# AA_Tone_Control.net
KiCad netlist of a schematic drawn in Altium Designer
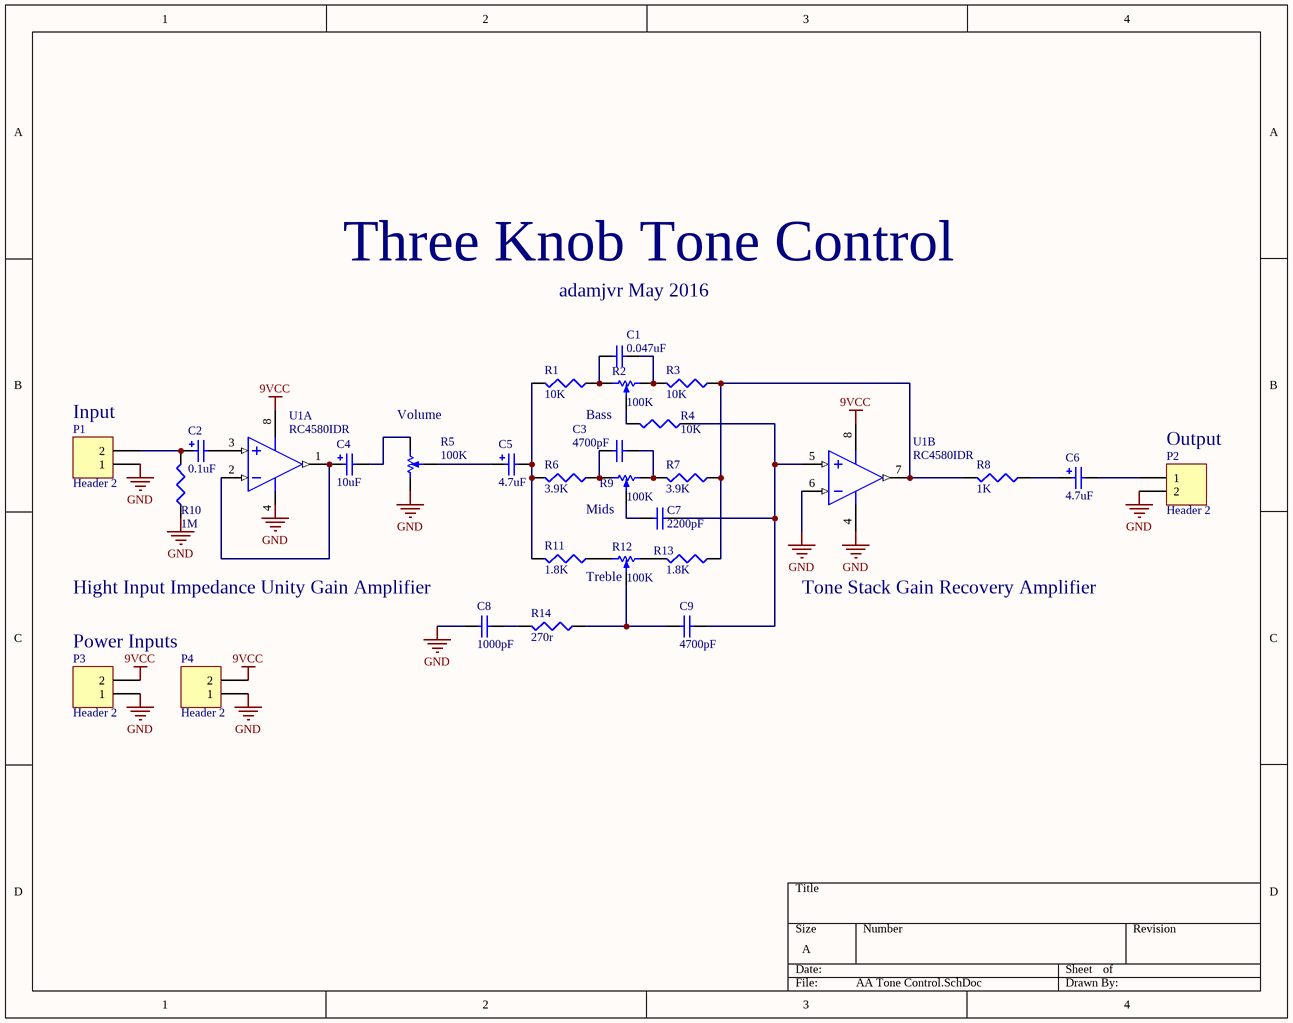
[diagram p0: AA Tone Control.SchDoc]

(export (version "E")
  (design (tool "Eeschema 10.0.6"))
  (components
    (comp (ref "C1")
      (value "0.047uF")
      (footprint "K473K15X7RF5TH5")
      (fields
        (field (name "MFR") "Vishay BC Components")
        (field (name "TOLERANCE") "10%")
        (field (name "VOLTAGE") "50V")
        (field (name "DESIGNER") "Adam Vadala-Roth")
      )
      (libsource (lib "AudioPartLib") (part "K473K15X7RF5TH5"))
    )
    (comp (ref "C2")
      (value "0.1uF")
      (footprint "4X6mmCAP")
      (description "CAP ALUM 0.1UF 20% 50V RADIAL")
      (fields
        (field (name "MFR") "Nichion")
        (field (name "TOLERANCE") "20%")
        (field (name "DESIGNER") "Adam Vadala-Roth")
      )
      (libsource (lib "AudioPartLib") (part "UMW1H0R1MDD1TP"))
    )
    (comp (ref "C3")
      (value "4700pF")
      (footprint "VY2472M49Y5US63V7")
      (fields
        (field (name "MFR") "Vishay-BC-Components")
        (field (name "TOLERANCE") "20%")
        (field (name "VOLTAGE") "440VAC")
        (field (name "DESIGNER") "Adam Vadala-Roth")
      )
      (libsource (lib "AudioPartLib") (part "VY2472M49Y5US63V7"))
    )
    (comp (ref "C4")
      (value "10uF")
      (footprint "5X12.5mmCAP - GREEN")
      (description "CAP ALUM 10UF 20% 25V RADIAL")
      (fields
        (field (name "MFR") "Nichicon")
        (field (name "TOLERANCE") "20%")
        (field (name "DESIGNER") "Adam Vadala-Roth")
      )
      (libsource (lib "AudioPartLib") (part "UES1E100MDM1TD"))
    )
    (comp (ref "C5")
      (value "4.7uF")
      (footprint "4X6mmCAP")
      (description "CAP ALUM 4.7UF 20% 35V RADIAL")
      (fields
        (field (name "MFR") "Nichicon")
        (field (name "TOLERANCE") "20%")
        (field (name "DESIGNER") "Adam Vadala-Roth")
      )
      (libsource (lib "AudioPartLib") (part "UMW1V4R7MDD1TP"))
    )
    (comp (ref "C6")
      (value "4.7uF")
      (footprint "4X6mmCAP")
      (description "CAP ALUM 4.7UF 20% 35V RADIAL")
      (fields
        (field (name "MFR") "Nichicon")
        (field (name "TOLERANCE") "20%")
        (field (name "DESIGNER") "Adam Vadala-Roth")
      )
      (libsource (lib "AudioPartLib") (part "UMW1V4R7MDD1TP"))
    )
    (comp (ref "C7")
      (value "2200pF")
      (footprint "VY1222M47Y5UQ63V0")
      (fields
        (field (name "MFR") "Vishay-BC-Components")
        (field (name "TOLERANCE") "20%")
        (field (name "VOLTAGE") "760VAC")
        (field (name "DESIGNER") "Adam Vadala-Roth")
      )
      (libsource (lib "AudioPartLib") (part "VY1222M47Y5UQ63V0"))
    )
    (comp (ref "C8")
      (value "1000pF")
      (footprint "VY2102M29Y5US63V7")
      (fields
        (field (name "MFR") "Vishay-BC-Components")
        (field (name "TOLERANCE") "20%")
        (field (name "VOLTAGE") "440VAC")
        (field (name "DESIGNER") "Adam Vadala-Roth")
      )
      (libsource (lib "AudioPartLib") (part "VY2102M29Y5US63V7"))
    )
    (comp (ref "C9")
      (value "4700pF")
      (footprint "VY2472M49Y5US63V7")
      (fields
        (field (name "MFR") "Vishay-BC-Components")
        (field (name "TOLERANCE") "20%")
        (field (name "VOLTAGE") "440VAC")
        (field (name "DESIGNER") "Adam Vadala-Roth")
      )
      (libsource (lib "AudioPartLib") (part "VY2472M49Y5US63V7"))
    )
    (comp (ref "P1")
      (value "Header 2")
      (footprint "HDR1X2")
      (description "Header, 2-Pin")
      (fields (field (name "PUBLISHER") "Altium Limited"))
      (libsource (lib "") (part "Header 2_1"))
    )
    (comp (ref "P2")
      (value "Header 2")
      (footprint "HDR1X2")
      (description "Header, 2-Pin")
      (fields (field (name "PUBLISHER") "Altium Limited"))
      (libsource (lib "Miscellaneous Connectors") (part "Header 2"))
    )
    (comp (ref "P3")
      (value "Header 2")
      (footprint "HDR1X2")
      (description "Header, 2-Pin")
      (fields (field (name "PUBLISHER") "Altium Limited"))
      (libsource (lib "") (part "Header 2_1"))
    )
    (comp (ref "P4")
      (value "Header 2")
      (footprint "HDR1X2")
      (description "Header, 2-Pin")
      (fields (field (name "PUBLISHER") "Altium Limited"))
      (libsource (lib "") (part "Header 2_1"))
    )
    (comp (ref "R1")
      (value "10K")
      (footprint "R0805")
      (description "RES SMD 10K OHM 1% 1/8W 0805")
      (fields
        (field (name "MFR") "Panasonic-Electronic-Components")
        (field (name "TOLERANCE") "1%")
        (field (name "DESIGNER") "Adam Vadala-Roth")
      )
      (libsource (lib "AudioPartLib") (part "ERJ-6ENF1002V"))
    )
    (comp (ref "R2")
      (value "100K")
      (footprint "BOURNS_PTD90SERIES_POT")
      (description "POT 100K OHM 1/20W CARBON LINEAR")
      (fields
        (field (name "MFR") "Bourns Inc.")
        (field (name "TOLERANCE") "20%")
        (field (name "DESIGNER") "Adam Vadala-Roth")
      )
      (libsource (lib "AudioPartLib") (part "PTD901-2015K-B104"))
    )
    (comp (ref "R3")
      (value "10K")
      (footprint "R0805")
      (description "RES SMD 10K OHM 1% 1/8W 0805")
      (fields
        (field (name "MFR") "Panasonic-Electronic-Components")
        (field (name "TOLERANCE") "1%")
        (field (name "DESIGNER") "Adam Vadala-Roth")
      )
      (libsource (lib "AudioPartLib") (part "ERJ-6ENF1002V"))
    )
    (comp (ref "R4")
      (value "10K")
      (footprint "R0805")
      (description "RES SMD 10K OHM 1% 1/8W 0805")
      (fields
        (field (name "MFR") "Panasonic-Electronic-Components")
        (field (name "TOLERANCE") "1%")
        (field (name "DESIGNER") "Adam Vadala-Roth")
      )
      (libsource (lib "AudioPartLib") (part "ERJ-6ENF1002V"))
    )
    (comp (ref "R5")
      (value "100K")
      (footprint "BOURNS_PTD90SERIES_POT")
      (description "POT 100K OHM 1/20W CARBON LINEAR")
      (fields
        (field (name "MFR") "Bourns Inc.")
        (field (name "TOLERANCE") "20%")
        (field (name "DESIGNER") "Adam Vadala-Roth")
      )
      (libsource (lib "AudioPartLib") (part "PTD901-2015K-B104"))
    )
    (comp (ref "R6")
      (value "3.9K")
      (footprint "R0805")
      (description "RES SMD 3.9K OHM 1% 1/8W 0805")
      (fields
        (field (name "MFR") "Samsung-Electro-Mechanics-America,-Inc.")
        (field (name "TOLERANCE") "1%")
        (field (name "DESIGNER") "Adam Vadala-Roth")
      )
      (libsource (lib "AudioPartLib") (part "RC2012F392CS"))
    )
    (comp (ref "R7")
      (value "3.9K")
      (footprint "R0805")
      (description "RES SMD 3.9K OHM 1% 1/8W 0805")
      (fields
        (field (name "MFR") "Samsung-Electro-Mechanics-America,-Inc.")
        (field (name "TOLERANCE") "1%")
        (field (name "DESIGNER") "Adam Vadala-Roth")
      )
      (libsource (lib "AudioPartLib") (part "RC2012F392CS"))
    )
    (comp (ref "R8")
      (value "1K")
      (footprint "R0805")
      (description "RES SMD 1K OHM 1% 1/8W 0805")
      (fields
        (field (name "MFR") "Samsung-Electro-Mechanics-America,-Inc.")
        (field (name "TOLERANCE") "1%")
        (field (name "DESIGNER") "Adam Vadala-Roth")
      )
      (libsource (lib "AudioPartLib") (part "RC2012F102CS"))
    )
    (comp (ref "R9")
      (value "100K")
      (footprint "BOURNS_PTD90SERIES_POT")
      (description "POT 100K OHM 1/20W CARBON LINEAR")
      (fields
        (field (name "MFR") "Bourns Inc.")
        (field (name "TOLERANCE") "20%")
        (field (name "DESIGNER") "Adam Vadala-Roth")
      )
      (libsource (lib "AudioPartLib") (part "PTD901-2015K-B104"))
    )
    (comp (ref "R10")
      (value "1M")
      (footprint "R0805")
      (description "RES SMD 1M OHM 5% 1/8W 0805")
      (fields
        (field (name "MFR") "Samsung-Electro-Mechanics-America,-Inc.")
        (field (name "TOLERANCE") "5%")
        (field (name "DESIGNER") "Adam Vadala-Roth")
      )
      (libsource (lib "AudioPartLib") (part "RC2012J105CS"))
    )
    (comp (ref "R11")
      (value "1.8K")
      (footprint "R0805")
      (description "RES SMD 1.8K OHM 1% 1/8W 0805")
      (fields
        (field (name "MFR") "Samsung-Electro-Mechanics-America,-Inc.")
        (field (name "TOLERANCE") "1%")
        (field (name "DESIGNER") "Adam Vadala-Roth")
      )
      (libsource (lib "AudioPartLib") (part "RC2012F182CS"))
    )
    (comp (ref "R12")
      (value "100K")
      (footprint "BOURNS_PTD90SERIES_POT")
      (description "POT 100K OHM 1/20W CARBON LINEAR")
      (fields
        (field (name "MFR") "Bourns Inc.")
        (field (name "TOLERANCE") "20%")
        (field (name "DESIGNER") "Adam Vadala-Roth")
      )
      (libsource (lib "AudioPartLib") (part "PTD901-2015K-B104"))
    )
    (comp (ref "R13")
      (value "1.8K")
      (footprint "R0805")
      (description "RES SMD 1.8K OHM 1% 1/8W 0805")
      (fields
        (field (name "MFR") "Samsung-Electro-Mechanics-America,-Inc.")
        (field (name "TOLERANCE") "1%")
        (field (name "DESIGNER") "Adam Vadala-Roth")
      )
      (libsource (lib "AudioPartLib") (part "RC2012F182CS"))
    )
    (comp (ref "R14")
      (value "270r")
      (footprint "R0805")
      (description "RES SMD 270 OHM 1% 1/8W 0805")
      (fields
        (field (name "MFR") "Samsung-Electro-Mechanics-America,-Inc.")
        (field (name "TOLERANCE") "1%")
        (field (name "DESIGNER") "Adam Vadala-Roth")
      )
      (libsource (lib "AudioPartLib") (part "RC2012F271CS"))
    )
    (comp (ref "U1")
      (value "RC4580IDR")
      (footprint "SOIC127P600X175-8N")
      (fields
        (field (name "MFR") "Texas Instruments")
        (field (name "VOLTAGE") "16V Max")
        (field (name "DESIGNER") "Adam Vadala-Roth")
      )
      (libsource (lib "AudioPartLib") (part "RC4580IDR"))
    )
  )
  (nets
    (net (code "1") (name "9VCC") (class "Default")
      (node (ref "P3") (pin "2") (pinfunction "2_2") (pintype "passive"))
      (node (ref "P4") (pin "2") (pinfunction "2_2") (pintype "passive"))
      (node (ref "U1") (pin "8") (pinfunction "V+_8") (pintype "power_in"))
    )
    (net (code "2") (name "GND") (class "Default")
      (node (ref "C8") (pin "2") (pinfunction "2_2") (pintype "passive"))
      (node (ref "P1") (pin "1") (pinfunction "1_1") (pintype "passive"))
      (node (ref "P2") (pin "2") (pinfunction "2_2") (pintype "passive"))
      (node (ref "P3") (pin "1") (pinfunction "1_1") (pintype "passive"))
      (node (ref "P4") (pin "1") (pinfunction "1_1") (pintype "passive"))
      (node (ref "R10") (pin "1") (pinfunction "1_1") (pintype "passive"))
      (node (ref "R5") (pin "3") (pinfunction "3_3") (pintype "passive"))
      (node (ref "U1") (pin "4") (pinfunction "V-_4") (pintype "power_in"))
      (node (ref "U1") (pin "6") (pinfunction "IN_B_6") (pintype "input"))
    )
    (net (code "3") (name "Net-(C1-Pad1)") (class "Default")
      (node (ref "C1") (pin "1") (pinfunction "1_1") (pintype "passive"))
      (node (ref "R2") (pin "1") (pinfunction "1_1") (pintype "passive"))
      (node (ref "R3") (pin "2") (pinfunction "2_2") (pintype "passive"))
    )
    (net (code "4") (name "Net-(C1-Pad2)") (class "Default")
      (node (ref "C1") (pin "2") (pinfunction "2_2") (pintype "passive"))
      (node (ref "R1") (pin "1") (pinfunction "1_1") (pintype "passive"))
      (node (ref "R2") (pin "3") (pinfunction "3_3") (pintype "passive"))
    )
    (net (code "5") (name "Net-(C2-Pad1)") (class "Default")
      (node (ref "C2") (pin "1") (pinfunction "1_1") (pintype "passive"))
      (node (ref "P1") (pin "2") (pinfunction "2_2") (pintype "passive"))
      (node (ref "R10") (pin "2") (pinfunction "2_2") (pintype "passive"))
    )
    (net (code "6") (name "Net-(C2-Pad2)") (class "Default")
      (node (ref "C2") (pin "2") (pinfunction "2_2") (pintype "passive"))
      (node (ref "U1") (pin "3") (pinfunction "IN_A_3") (pintype "input"))
    )
    (net (code "7") (name "Net-(C3-Pad1)") (class "Default")
      (node (ref "C3") (pin "1") (pinfunction "1_1") (pintype "passive"))
      (node (ref "R7") (pin "2") (pinfunction "2_2") (pintype "passive"))
      (node (ref "R9") (pin "1") (pinfunction "1_1") (pintype "passive"))
    )
    (net (code "8") (name "Net-(C3-Pad2)") (class "Default")
      (node (ref "C3") (pin "2") (pinfunction "2_2") (pintype "passive"))
      (node (ref "R6") (pin "1") (pinfunction "1_1") (pintype "passive"))
      (node (ref "R9") (pin "3") (pinfunction "3_3") (pintype "passive"))
    )
    (net (code "9") (name "Net-(C4-Pad2)") (class "Default")
      (node (ref "C4") (pin "2") (pinfunction "2_2") (pintype "passive"))
      (node (ref "R5") (pin "1") (pinfunction "1_1") (pintype "passive"))
    )
    (net (code "10") (name "Net-(C5-Pad1)") (class "Default")
      (node (ref "C5") (pin "1") (pinfunction "1_1") (pintype "passive"))
      (node (ref "R5") (pin "2") (pinfunction "2_2") (pintype "passive"))
    )
    (net (code "11") (name "Net-(C5-Pad2)") (class "Default")
      (node (ref "C5") (pin "2") (pinfunction "2_2") (pintype "passive"))
      (node (ref "R1") (pin "2") (pinfunction "2_2") (pintype "passive"))
      (node (ref "R11") (pin "2") (pinfunction "2_2") (pintype "passive"))
      (node (ref "R6") (pin "2") (pinfunction "2_2") (pintype "passive"))
    )
    (net (code "12") (name "Net-(C6-Pad1)") (class "Default")
      (node (ref "C6") (pin "1") (pinfunction "1_1") (pintype "passive"))
      (node (ref "R8") (pin "1") (pinfunction "1_1") (pintype "passive"))
    )
    (net (code "13") (name "Net-(C6-Pad2)") (class "Default")
      (node (ref "C6") (pin "2") (pinfunction "2_2") (pintype "passive"))
      (node (ref "P2") (pin "1") (pinfunction "1_1") (pintype "passive"))
    )
    (net (code "14") (name "Net-(C7-Pad1)") (class "Default")
      (node (ref "C7") (pin "1") (pinfunction "1_1") (pintype "passive"))
      (node (ref "C9") (pin "1") (pinfunction "1_1") (pintype "passive"))
      (node (ref "R4") (pin "1") (pinfunction "1_1") (pintype "passive"))
      (node (ref "U1") (pin "5") (pinfunction "IN_B_5") (pintype "input"))
    )
    (net (code "15") (name "Net-(C7-Pad2)") (class "Default")
      (node (ref "C7") (pin "2") (pinfunction "2_2") (pintype "passive"))
      (node (ref "R9") (pin "2") (pinfunction "2_2") (pintype "passive"))
    )
    (net (code "16") (name "Net-(C8-Pad1)") (class "Default")
      (node (ref "C8") (pin "1") (pinfunction "1_1") (pintype "passive"))
      (node (ref "R14") (pin "2") (pinfunction "2_2") (pintype "passive"))
    )
    (net (code "17") (name "Net-(C9-Pad2)") (class "Default")
      (node (ref "C9") (pin "2") (pinfunction "2_2") (pintype "passive"))
      (node (ref "R12") (pin "2") (pinfunction "2_2") (pintype "passive"))
      (node (ref "R14") (pin "1") (pinfunction "1_1") (pintype "passive"))
    )
    (net (code "18") (name "Net-(R2-Pad2)") (class "Default")
      (node (ref "R2") (pin "2") (pinfunction "2_2") (pintype "passive"))
      (node (ref "R4") (pin "2") (pinfunction "2_2") (pintype "passive"))
    )
    (net (code "19") (name "Net-(R11-Pad1)") (class "Default")
      (node (ref "R11") (pin "1") (pinfunction "1_1") (pintype "passive"))
      (node (ref "R12") (pin "3") (pinfunction "3_3") (pintype "passive"))
    )
    (net (code "20") (name "Net-(R12-Pad1)") (class "Default")
      (node (ref "R12") (pin "1") (pinfunction "1_1") (pintype "passive"))
      (node (ref "R13") (pin "2") (pinfunction "2_2") (pintype "passive"))
    )
    (net (code "21") (name "Net-(U1A-OUT_A)") (class "Default")
      (node (ref "C4") (pin "1") (pinfunction "1_1") (pintype "passive"))
      (node (ref "U1") (pin "1") (pinfunction "OUT_A_1") (pintype "output"))
      (node (ref "U1") (pin "2") (pinfunction "IN_A_2") (pintype "input"))
    )
    (net (code "22") (name "Net-(U1B-OUT_B)") (class "Default")
      (node (ref "R13") (pin "1") (pinfunction "1_1") (pintype "passive"))
      (node (ref "R3") (pin "1") (pinfunction "1_1") (pintype "passive"))
      (node (ref "R7") (pin "1") (pinfunction "1_1") (pintype "passive"))
      (node (ref "R8") (pin "2") (pinfunction "2_2") (pintype "passive"))
      (node (ref "U1") (pin "7") (pinfunction "OUT_B_7") (pintype "output"))
    )
    (net (code "23") (name "unconnected-(U1A-V--Pad4)") (class "Default")
      (node (ref "U1") (pin "4") (pinfunction "V-_4") (pintype "power_in"))
    )
  )
)
